# HVSchematic.net
KiCad netlist of a schematic drawn in Altium Designer
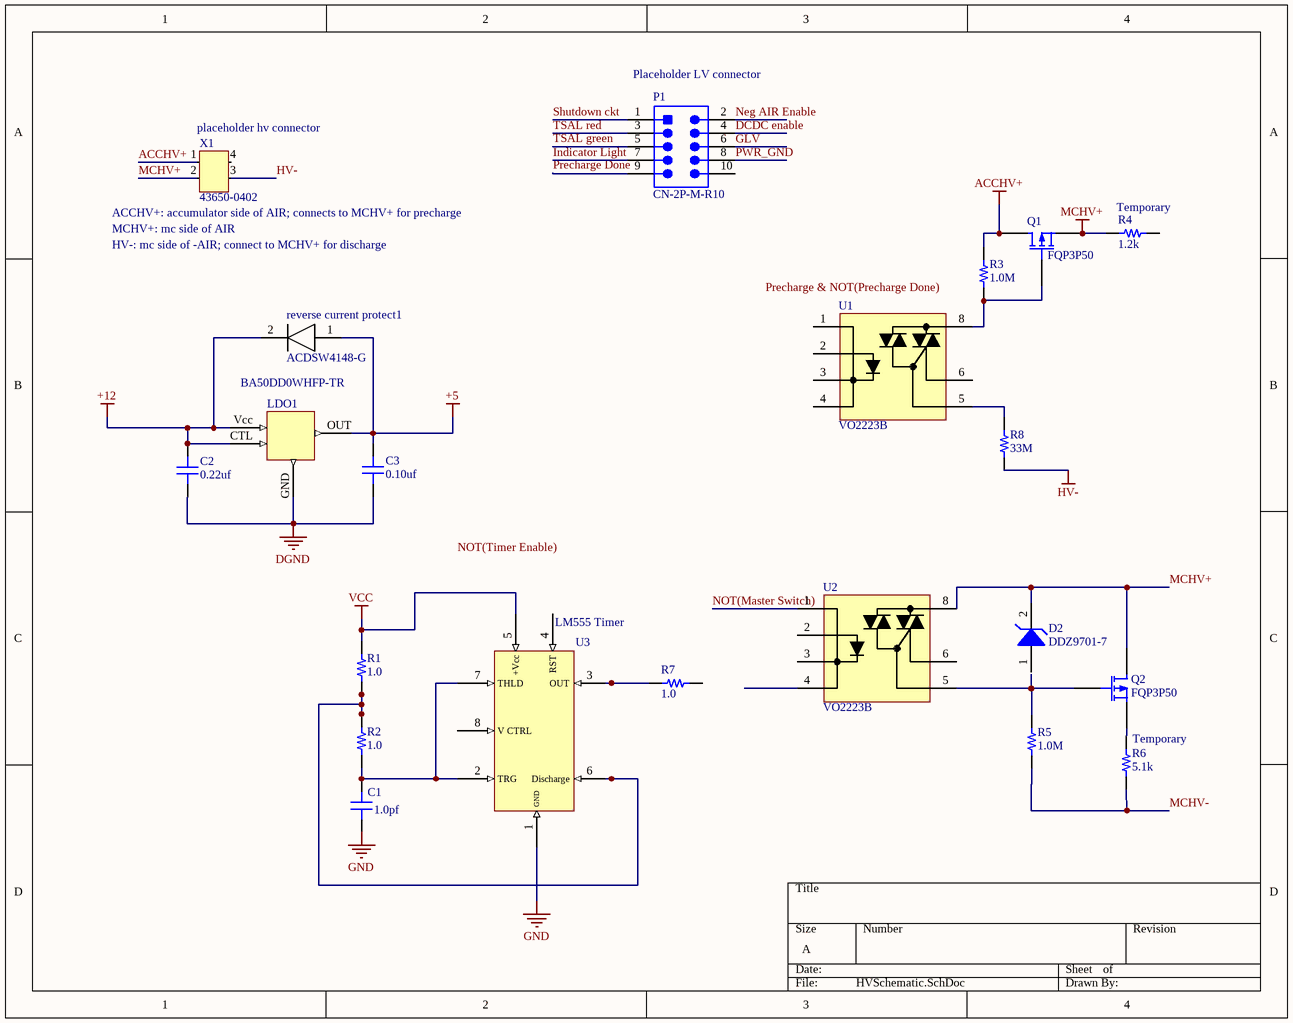
[diagram p0: HVSchematic.SchDoc]

(export (version "E")
  (design (tool "Eeschema 10.0.6"))
  (components
    (comp (ref "C1")
      (value "1.0pf")
      (footprint "CAP 0402/1005")
      (fields
        (field (name "Comment") "Capacitor MLCC 1.0pf 16V CAP 0402/1005")
        (field (name "CREATED_BY") "Nick Mah")
      )
      (libsource (lib "Altium-Lib") (part "Capacitor"))
    )
    (comp (ref "C2")
      (value "0.22uf")
      (footprint "CAP 0805/2012")
      (fields
        (field (name "Comment") "Capacitor MLCC 0.22uf 50V CAP 0805/2012")
        (field (name "CREATED_BY") "Nick Mah")
      )
      (libsource (lib "Altium-Lib") (part "Capacitor"))
    )
    (comp (ref "C3")
      (value "0.10uf")
      (footprint "CAP 0805/2012")
      (fields
        (field (name "Comment") "Capacitor MLCC 0.10uf 50V CAP 0805/2012")
        (field (name "CREATED_BY") "Nick Mah")
      )
      (libsource (lib "Altium-Lib") (part "Capacitor"))
    )
    (comp (ref "D2")
      (value "DDZ9701-7")
      (footprint "SOD123F")
      (description "Zener Diode 14V 500mW ±5% Surface Mount SOD-123")
      (fields (field (name "POWER") "500mW"))
      (libsource (lib "Altium-Lib") (part "Zener"))
    )
    (comp (ref "LDO1")
      (value "BA50DD0WHFP-TR")
      (footprint "HRP5")
      (libsource (lib "Altium-Lib") (part "BA50DD0WHFP-TR Linear Voltage Regulators 5"))
    )
    (comp (ref "P1")
      (value "CN-2P-M-R10")
      (footprint "HDR2X5_SMT")
      (description "2 row connector")
      (fields (field (name "MFRPARTNO") "5103309-1") (field (name "CREATED_BY") "Aiku"))
      (libsource (lib "Altium-Lib") (part "CN-2P-M-R10"))
    )
    (comp (ref "Q1")
      (value "FQP3P50")
      (footprint "TO-220AB")
      (fields (field (name "CREATED_BY") "Angel"))
      (libsource (lib "Altium-Lib") (part "FQP3P50"))
    )
    (comp (ref "Q2")
      (value "FQP3P50")
      (footprint "TO-220AB")
      (fields (field (name "CREATED_BY") "Angel"))
      (libsource (lib "Altium-Lib") (part "FQP3P50"))
    )
    (comp (ref "R1")
      (value "1.0")
      (footprint "RES 0402/1005")
      (fields
        (field (name "TOLERANCE") "1%")
        (field (name "POWER") "1/10W")
        (field (name "Comment") "Resistor 1.0 0402 1/10W 1%")
        (field (name "CREATED_BY") "Nick Mah")
      )
      (libsource (lib "Altium-Lib") (part "Resistor"))
    )
    (comp (ref "R2")
      (value "1.0")
      (footprint "RES 0402/1005")
      (fields
        (field (name "TOLERANCE") "1%")
        (field (name "POWER") "1/10W")
        (field (name "Comment") "Resistor 1.0 0402 1/10W 1%")
        (field (name "CREATED_BY") "Nick Mah")
      )
      (libsource (lib "Altium-Lib") (part "Resistor"))
    )
    (comp (ref "R3")
      (value "1.0M")
      (footprint "RES 0603/1608")
      (fields
        (field (name "TOLERANCE") "10%")
        (field (name "POWER") "1/10W")
        (field (name "Comment") "Resistor 1.0M 0603 1/10W 10%")
        (field (name "CREATED_BY") "Nick Mah")
      )
      (libsource (lib "Altium-Lib") (part "Resistor"))
    )
    (comp (ref "R4")
      (value "Temporary")
      (footprint "RES 0603/1608")
      (fields
        (field (name "ALTIUM_VALUE") "1.2k")
        (field (name "TOLERANCE") "10%")
        (field (name "POWER") "1/10W")
        (field (name "CREATED_BY") "Nick Mah")
      )
      (libsource (lib "Altium-Lib") (part "Resistor"))
    )
    (comp (ref "R5")
      (value "1.0M")
      (footprint "RES 0603/1608")
      (fields
        (field (name "TOLERANCE") "1%")
        (field (name "POWER") "1/10W")
        (field (name "Comment") "Resistor 1.0M 0603 1/10W 1%")
        (field (name "CREATED_BY") "Nick Mah")
      )
      (libsource (lib "Altium-Lib") (part "Resistor"))
    )
    (comp (ref "R6")
      (value "Temporary")
      (footprint "RES 0603/1608")
      (fields
        (field (name "ALTIUM_VALUE") "5.1k")
        (field (name "TOLERANCE") "1%")
        (field (name "POWER") "1/10W")
        (field (name "CREATED_BY") "Nick Mah")
      )
      (libsource (lib "Altium-Lib") (part "Resistor"))
    )
    (comp (ref "R7")
      (value "1.0")
      (footprint "RES 0402/1005")
      (fields
        (field (name "TOLERANCE") "1%")
        (field (name "POWER") "1/10W")
        (field (name "Comment") "Resistor 1.0 0402 1/10W 1%")
        (field (name "CREATED_BY") "Nick Mah")
      )
      (libsource (lib "Altium-Lib") (part "Resistor"))
    )
    (comp (ref "R8")
      (value "33M")
      (footprint "RES 0603/1608")
      (fields
        (field (name "TOLERANCE") "10%")
        (field (name "POWER") "1/10W")
        (field (name "Comment") "Resistor 33M 0603 1/10W 10%")
        (field (name "CREATED_BY") "Nick Mah")
      )
      (libsource (lib "Altium-Lib") (part "Resistor"))
    )
    (comp (ref "reverse current protect1")
      (value "ACDSW4148-G")
      (footprint "DIODE SOD123")
      (libsource (lib "Altium-Lib") (part "ACDSW4148-G Swtiching Diode"))
    )
    (comp (ref "U1")
      (value "VO2223B")
      (footprint "Option 7")
      (description "Optocoupler, Power Phototriac")
      (libsource (lib "Altium-Lib") (part "VO2223B"))
    )
    (comp (ref "U2")
      (value "VO2223B")
      (footprint "Option 7")
      (description "Optocoupler, Power Phototriac")
      (libsource (lib "Altium-Lib") (part "VO2223B"))
    )
    (comp (ref "U3")
      (value "LM555 Timer")
      (footprint "SOIC-8")
      (libsource (lib "Altium-Lib") (part "LM555 Timer"))
    )
    (comp (ref "X1")
      (value "43650-0402")
      (footprint "Molex_43650_0402")
      (fields (field (name "CREATED_BY") "Nick"))
      (libsource (lib "Altium-Lib") (part "CONN 4POS"))
    )
  )
  (nets
    (net (code "1") (name "+5") (class "Default")
      (node (ref "C3") (pin "2") (pinfunction "2_2") (pintype "passive"))
      (node (ref "LDO1") (pin "OUT") (pintype "output"))
      (node (ref "reverse current protect1") (pin "1") (pintype "passive"))
    )
    (net (code "2") (name "+12") (class "Default")
      (node (ref "C2") (pin "2") (pinfunction "2_2") (pintype "passive"))
      (node (ref "LDO1") (pin "CTL") (pintype "input"))
      (node (ref "LDO1") (pin "Vcc") (pintype "input"))
      (node (ref "reverse current protect1") (pin "2") (pintype "passive"))
    )
    (net (code "3") (name "/DCDC enable") (class "Default")
      (node (ref "P1") (pin "4") (pinfunction "4_4") (pintype "passive"))
    )
    (net (code "4") (name "/GLV") (class "Default")
      (node (ref "P1") (pin "6") (pinfunction "6_6") (pintype "passive"))
    )
    (net (code "5") (name "/Indicator Light") (class "Default")
      (node (ref "P1") (pin "7") (pinfunction "7_7") (pintype "passive"))
    )
    (net (code "6") (name "/MCHV-") (class "Default")
      (node (ref "R5") (pin "1") (pinfunction "1_1") (pintype "passive"))
      (node (ref "R6") (pin "1") (pinfunction "1_1") (pintype "passive"))
    )
    (net (code "7") (name "/NOT(Master Switch)") (class "Default")
      (node (ref "U2") (pin "1") (pintype "power_in"))
    )
    (net (code "9") (name "/Neg AIR Enable") (class "Default")
      (node (ref "P1") (pin "2") (pinfunction "2_2") (pintype "passive"))
    )
    (net (code "10") (name "/PWR_GND") (class "Default")
      (node (ref "P1") (pin "8") (pinfunction "8_8") (pintype "passive"))
    )
    (net (code "12") (name "/Precharge Done") (class "Default")
      (node (ref "P1") (pin "9") (pinfunction "9_9") (pintype "passive"))
    )
    (net (code "13") (name "/Shutdown ckt") (class "Default")
      (node (ref "P1") (pin "1") (pinfunction "1_1") (pintype "passive"))
    )
    (net (code "14") (name "/TSAL green") (class "Default")
      (node (ref "P1") (pin "5") (pinfunction "5_5") (pintype "passive"))
    )
    (net (code "15") (name "/TSAL red") (class "Default")
      (node (ref "P1") (pin "3") (pinfunction "3_3") (pintype "passive"))
    )
    (net (code "16") (name "ACCHV+") (class "Default")
      (node (ref "Q1") (pin "2") (pinfunction "D_2") (pintype "passive"))
      (node (ref "R3") (pin "1") (pinfunction "1_1") (pintype "passive"))
      (node (ref "X1") (pin "1") (pintype "input"))
    )
    (net (code "17") (name "DGND") (class "Default")
      (node (ref "C2") (pin "1") (pinfunction "1_1") (pintype "passive"))
      (node (ref "C3") (pin "1") (pinfunction "1_1") (pintype "passive"))
      (node (ref "LDO1") (pin "GND") (pintype "output"))
    )
    (net (code "18") (name "GND") (class "Default")
      (node (ref "U3") (pin "1") (pinfunction "GND_1") (pintype "input"))
    )
    (net (code "19") (name "HV-") (class "Default")
      (node (ref "R8") (pin "1") (pinfunction "1_1") (pintype "passive"))
      (node (ref "X1") (pin "3") (pintype "input"))
    )
    (net (code "20") (name "MCHV+") (class "Default")
      (node (ref "D2") (pin "2") (pinfunction "K_2") (pintype "passive"))
      (node (ref "Q1") (pin "3") (pinfunction "S_3") (pintype "passive"))
      (node (ref "Q2") (pin "2") (pinfunction "D_2") (pintype "passive"))
      (node (ref "R4") (pin "1") (pinfunction "1_1") (pintype "passive"))
      (node (ref "U2") (pin "8") (pintype "power_in"))
      (node (ref "X1") (pin "2") (pintype "input"))
    )
    (net (code "21") (name "Net-(Q1-G)") (class "Default")
      (node (ref "Q1") (pin "1") (pinfunction "G_1") (pintype "passive"))
      (node (ref "R3") (pin "2") (pinfunction "2_2") (pintype "passive"))
      (node (ref "U1") (pin "8") (pintype "power_in"))
    )
    (net (code "22") (name "Net-(Q2-G)") (class "Default")
      (node (ref "Q2") (pin "1") (pinfunction "G_1") (pintype "passive"))
      (node (ref "R5") (pin "2") (pinfunction "2_2") (pintype "passive"))
      (node (ref "U2") (pin "5") (pintype "power_in"))
    )
    (net (code "23") (name "Net-(Q2-S)") (class "Default")
      (node (ref "Q2") (pin "3") (pinfunction "S_3") (pintype "passive"))
      (node (ref "R6") (pin "2") (pinfunction "2_2") (pintype "passive"))
    )
    (net (code "24") (name "Net-(R8-Pad2)") (class "Default")
      (node (ref "R8") (pin "2") (pinfunction "2_2") (pintype "passive"))
      (node (ref "U1") (pin "5") (pintype "power_in"))
    )
    (net (code "25") (name "Net-(U3-Discharge)") (class "Default")
      (node (ref "R1") (pin "1") (pinfunction "1_1") (pintype "passive"))
      (node (ref "R2") (pin "1") (pinfunction "1_1") (pintype "passive"))
      (node (ref "U3") (pin "6") (pinfunction "Discharge_6") (pintype "input"))
    )
    (net (code "26") (name "Net-(U3-OUT)") (class "Default")
      (node (ref "R7") (pin "1") (pinfunction "1_1") (pintype "passive"))
      (node (ref "U3") (pin "3") (pinfunction "OUT_3") (pintype "input"))
    )
    (net (code "27") (name "Net-(U3-THLD)") (class "Default")
      (node (ref "C1") (pin "2") (pinfunction "2_2") (pintype "passive"))
      (node (ref "R2") (pin "2") (pinfunction "2_2") (pintype "passive"))
      (node (ref "U3") (pin "2") (pinfunction "TRG_2") (pintype "input"))
      (node (ref "U3") (pin "7") (pinfunction "THLD_7") (pintype "input"))
    )
    (net (code "28") (name "VCC") (class "Default")
      (node (ref "R1") (pin "2") (pinfunction "2_2") (pintype "passive"))
      (node (ref "U3") (pin "5") (pinfunction "+Vcc_5") (pintype "input"))
    )
    (net (code "29") (name "unconnected-(C1-Pad1)") (class "Default")
      (node (ref "C1") (pin "1") (pinfunction "1_1") (pintype "passive"))
    )
    (net (code "30") (name "unconnected-(D2-A-Pad1)") (class "Default")
      (node (ref "D2") (pin "1") (pinfunction "A_1") (pintype "passive"))
    )
    (net (code "31") (name "unconnected-(P1-Pad10)") (class "Default")
      (node (ref "P1") (pin "10") (pinfunction "10_10") (pintype "passive"))
    )
    (net (code "32") (name "unconnected-(R4-Pad2)") (class "Default")
      (node (ref "R4") (pin "2") (pinfunction "2_2") (pintype "passive"))
    )
    (net (code "33") (name "unconnected-(R7-Pad2)") (class "Default")
      (node (ref "R7") (pin "2") (pinfunction "2_2") (pintype "passive"))
    )
    (net (code "34") (name "unconnected-(U1-Pad1)") (class "Default")
      (node (ref "U1") (pin "1") (pintype "power_in"))
    )
    (net (code "35") (name "unconnected-(U1-Pad2)") (class "Default")
      (node (ref "U1") (pin "2") (pintype "power_in"))
    )
    (net (code "36") (name "unconnected-(U1-Pad3)") (class "Default")
      (node (ref "U1") (pin "3") (pintype "power_in"))
    )
    (net (code "37") (name "unconnected-(U1-Pad4)") (class "Default")
      (node (ref "U1") (pin "4") (pintype "power_in"))
    )
    (net (code "38") (name "unconnected-(U1-Pad6)") (class "Default")
      (node (ref "U1") (pin "6") (pintype "power_in"))
    )
    (net (code "39") (name "unconnected-(U2-Pad2)") (class "Default")
      (node (ref "U2") (pin "2") (pintype "power_in"))
    )
    (net (code "40") (name "unconnected-(U2-Pad3)") (class "Default")
      (node (ref "U2") (pin "3") (pintype "power_in"))
    )
    (net (code "41") (name "unconnected-(U2-Pad4)") (class "Default")
      (node (ref "U2") (pin "4") (pintype "power_in"))
    )
    (net (code "42") (name "unconnected-(U2-Pad6)") (class "Default")
      (node (ref "U2") (pin "6") (pintype "power_in"))
    )
    (net (code "43") (name "unconnected-(U3-RST-Pad4)") (class "Default")
      (node (ref "U3") (pin "4") (pinfunction "RST_4") (pintype "input"))
    )
    (net (code "44") (name "unconnected-(U3-V_CTRL-Pad8)") (class "Default")
      (node (ref "U3") (pin "8") (pinfunction "V_CTRL_8") (pintype "input"))
    )
    (net (code "45") (name "unconnected-(X1-Pad4)") (class "Default")
      (node (ref "X1") (pin "4") (pintype "input"))
    )
  )
)
